# Multivibrator.net
KiCad netlist of a schematic drawn in Altium Designer
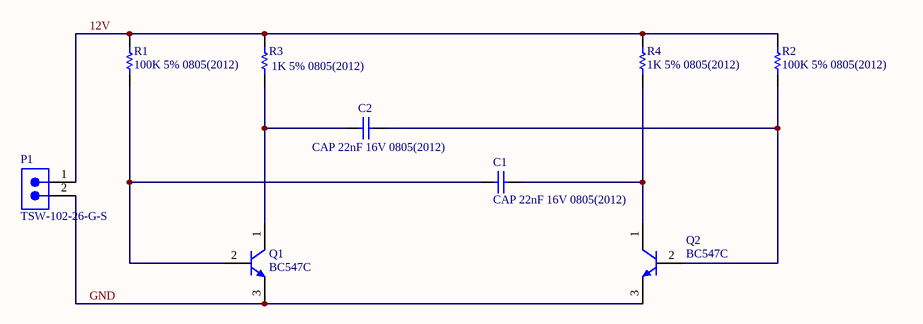
[diagram p0: Multivibrator.SchDoc]

(export (version "E")
  (design (tool "Eeschema 10.0.6"))
  (components
    (comp (ref "C1")
      (value "CAP 22nF 16V 0805(2012)")
      (footprint "CAPC0805(2012)145_N")
      (description "CAP 22nF 16V ±10% 0805 (2012 Metric) Thickness 1.45mm SMD")
      (fields (field (name "TOLERANCE") "Â±10%"))
      (libsource (lib "Altium Content Vault") (part "CAP"))
    )
    (comp (ref "C2")
      (value "CAP 22nF 16V 0805(2012)")
      (footprint "CAPC0805(2012)145_N")
      (description "CAP 22nF 16V ±10% 0805 (2012 Metric) Thickness 1.45mm SMD")
      (fields (field (name "TOLERANCE") "Â±10%"))
      (libsource (lib "Altium Content Vault") (part "CAP"))
    )
    (comp (ref "P1")
      (value "TSW-102-26-G-S")
      (footprint "SMTC-TSW-102-26-XX-S")
      (description "0.025\" SQ Post Header, Through-hole, Vertical, -55 to 125 degC, 2.54 mm Pitch, 2-Pin, Male, RoHS")
      (fields (field (name "MANUFACTURER") "Samtec"))
      (libsource (lib "Altium Content Vault") (part "SMTC-TSW-102-X-X-S-X"))
    )
    (comp (ref "Q1")
      (value "BC547C")
      (footprint "ONSC-TO-92-3-29-11")
      (description "Amplifier Transistor, NPN Silicon, 3-Pin TO-92, Bulk Box")
      (fields (field (name "MANUFACTURER") "On Semiconductor"))
      (libsource (lib "Altium Content Vault") (part "ONSC-NPN-C1B2E3-3"))
    )
    (comp (ref "Q2")
      (value "BC547C")
      (footprint "ONSC-TO-92-3-29-11")
      (description "Amplifier Transistor, NPN Silicon, 3-Pin TO-92, Bulk Box")
      (fields (field (name "MANUFACTURER") "On Semiconductor"))
      (libsource (lib "Altium Content Vault") (part "ONSC-NPN-C1B2E3-3"))
    )
    (comp (ref "R1")
      (value "100K 5% 0805(2012)")
      (footprint "RESC0805(2012)_L")
      (description "100K 0.125W 5% 0805 (2012 Metric)  SMD")
      (fields (field (name "TOLERANCE") "5 %") (field (name "POWER") "0.125 W"))
      (libsource (lib "Altium Content Vault") (part "RES"))
    )
    (comp (ref "R2")
      (value "100K 5% 0805(2012)")
      (footprint "RESC0805(2012)_L")
      (description "100K 0.125W 5% 0805 (2012 Metric)  SMD")
      (fields (field (name "TOLERANCE") "5 %") (field (name "POWER") "0.125 W"))
      (libsource (lib "Altium Content Vault") (part "RES"))
    )
    (comp (ref "R3")
      (value "1K 5% 0805(2012)")
      (footprint "RESC0805(2012)_N")
      (description "1K 0.125W 5% 0805 (2012 Metric)  SMD")
      (fields (field (name "POWER") "0.125 W") (field (name "TOLERANCE") "5 %"))
      (libsource (lib "Altium Content Vault") (part "RES"))
    )
    (comp (ref "R4")
      (value "1K 5% 0805(2012)")
      (footprint "RESC0805(2012)_N")
      (description "1K 0.125W 5% 0805 (2012 Metric)  SMD")
      (fields (field (name "POWER") "0.125 W") (field (name "TOLERANCE") "5 %"))
      (libsource (lib "Altium Content Vault") (part "RES"))
    )
  )
  (nets
    (net (code "1") (name "/12V") (class "Default")
      (node (ref "P1") (pin "1") (pinfunction "1_1") (pintype "passive"))
      (node (ref "R1") (pin "2") (pinfunction "2_2") (pintype "passive"))
      (node (ref "R2") (pin "2") (pinfunction "2_2") (pintype "passive"))
      (node (ref "R3") (pin "2") (pinfunction "2_2") (pintype "passive"))
      (node (ref "R4") (pin "2") (pinfunction "2_2") (pintype "passive"))
    )
    (net (code "2") (name "/GND") (class "Default")
      (node (ref "P1") (pin "2") (pinfunction "2_2") (pintype "passive"))
      (node (ref "Q1") (pin "3") (pinfunction "E_3") (pintype "passive"))
      (node (ref "Q2") (pin "3") (pinfunction "E_3") (pintype "passive"))
    )
    (net (code "3") (name "Net-(Q1-B)") (class "Default")
      (node (ref "C1") (pin "1") (pinfunction "1_1") (pintype "passive"))
      (node (ref "Q1") (pin "2") (pinfunction "B_2") (pintype "passive"))
      (node (ref "R1") (pin "1") (pinfunction "1_1") (pintype "passive"))
    )
    (net (code "4") (name "Net-(Q1-C)") (class "Default")
      (node (ref "C2") (pin "1") (pinfunction "1_1") (pintype "passive"))
      (node (ref "Q1") (pin "1") (pinfunction "C_1") (pintype "passive"))
      (node (ref "R3") (pin "1") (pinfunction "1_1") (pintype "passive"))
    )
    (net (code "5") (name "Net-(Q2-B)") (class "Default")
      (node (ref "C2") (pin "2") (pinfunction "2_2") (pintype "passive"))
      (node (ref "Q2") (pin "2") (pinfunction "B_2") (pintype "passive"))
      (node (ref "R2") (pin "1") (pinfunction "1_1") (pintype "passive"))
    )
    (net (code "6") (name "Net-(Q2-C)") (class "Default")
      (node (ref "C1") (pin "2") (pinfunction "2_2") (pintype "passive"))
      (node (ref "Q2") (pin "1") (pinfunction "C_1") (pintype "passive"))
      (node (ref "R4") (pin "1") (pinfunction "1_1") (pintype "passive"))
    )
  )
)
